# mapleCUx_med_022.net
KiCad netlist of a schematic drawn in EAGLE
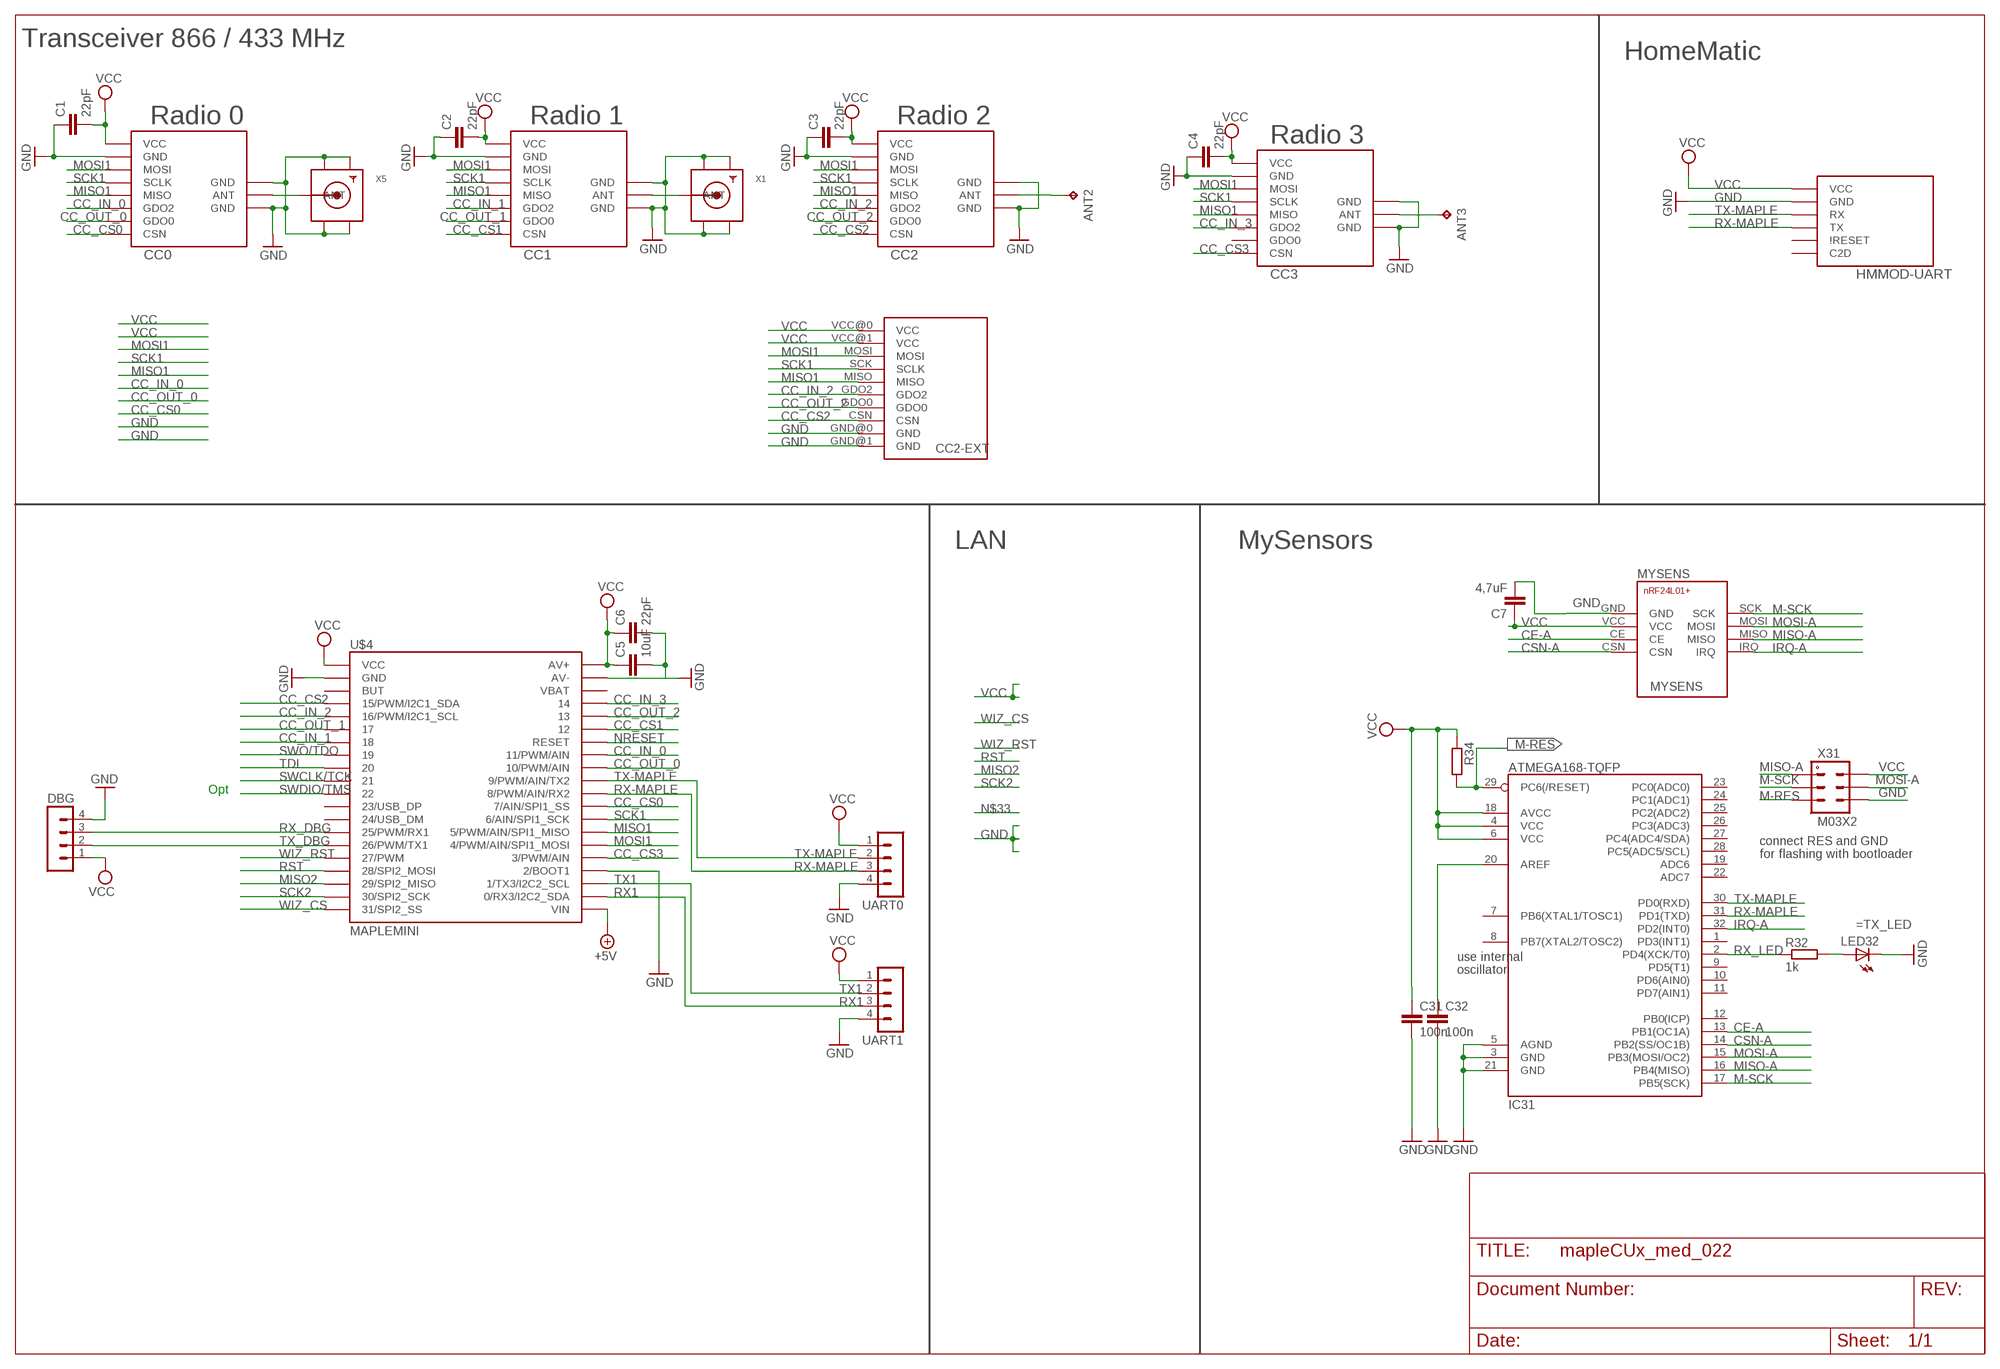
[diagram p0: schematic, sheet 1]

(export (version "E")
  (design (tool "Eeschema 10.0.6"))
  (components
    (comp (ref "ANT2")
      (value "TPPAD1-13")
      (footprint "eagle-import:P1-13")
      (libsource (lib "eagle-import") (part "TPPAD1-13"))
    )
    (comp (ref "ANT3")
      (value "TPPAD1-13")
      (footprint "eagle-import:P1-13")
      (libsource (lib "eagle-import") (part "TPPAD1-13"))
    )
    (comp (ref "C1")
      (value "22pF")
      (footprint "eagle-import:C0805")
      (libsource (lib "eagle-import") (part "C-EUC0805"))
    )
    (comp (ref "C2")
      (value "22pF")
      (footprint "eagle-import:C0805")
      (libsource (lib "eagle-import") (part "C-EUC0805"))
    )
    (comp (ref "C3")
      (value "22pF")
      (footprint "eagle-import:C0805")
      (libsource (lib "eagle-import") (part "C-EUC0805"))
    )
    (comp (ref "C4")
      (value "22pF")
      (footprint "eagle-import:C0805")
      (libsource (lib "eagle-import") (part "C-EUC0805"))
    )
    (comp (ref "C5")
      (value "10uF")
      (footprint "eagle-import:C1210")
      (libsource (lib "eagle-import") (part "C-EUC1210"))
    )
    (comp (ref "C6")
      (value "22pF")
      (footprint "eagle-import:C0805")
      (libsource (lib "eagle-import") (part "C-EUC0805"))
    )
    (comp (ref "C7")
      (value "4,7uF")
      (footprint "eagle-import:C1210")
      (libsource (lib "eagle-import") (part "C-EUC1210"))
    )
    (comp (ref "C31")
      (value "100n")
      (footprint "eagle-import:C0805")
      (libsource (lib "eagle-import") (part "C-EUC0805"))
    )
    (comp (ref "C32")
      (value "100n")
      (footprint "eagle-import:C0805")
      (libsource (lib "eagle-import") (part "C-EUC0805"))
    )
    (comp (ref "CC0")
      (value "CC1101")
      (footprint "eagle-import:CC1101_MODULE1_SMD")
      (libsource (lib "eagle-import") (part "CC1101_MODULE1SMD"))
    )
    (comp (ref "CC1")
      (value "CC1101_MODULE1SMD")
      (footprint "eagle-import:CC1101_MODULE1_SMD")
      (libsource (lib "eagle-import") (part "CC1101_MODULE1SMD"))
    )
    (comp (ref "CC2")
      (value "CC1101_MODULE1SMD")
      (footprint "eagle-import:CC1101_MODULE1_SMD")
      (libsource (lib "eagle-import") (part "CC1101_MODULE1SMD"))
    )
    (comp (ref "CC2-EXT")
      (value "CC1101_MODULE3_DIL")
      (footprint "eagle-import:CC1101_MODULE3_DIL")
      (libsource (lib "eagle-import") (part "CC1101_MODULE3_DIL"))
    )
    (comp (ref "CC3")
      (value "CC1101_MODULE1SMD")
      (footprint "eagle-import:CC1101_MODULE1_SMD")
      (libsource (lib "eagle-import") (part "CC1101_MODULE1SMD"))
    )
    (comp (ref "DBG")
      (value "MA04-1")
      (footprint "eagle-import:MA04-1")
      (libsource (lib "eagle-import") (part "MA04-1"))
    )
    (comp (ref "HMMOD-UART")
      (value "HM-MOD-UARTDIL")
      (footprint "eagle-import:HM-MOD-UART-DIL")
      (libsource (lib "eagle-import") (part "HM-MOD-UARTDIL"))
    )
    (comp (ref "IC31")
      (value "ATMEGA168-TQFP")
      (footprint "eagle-import:TQFP32-08")
      (libsource (lib "eagle-import") (part "ATMEGA168-TQFP"))
    )
    (comp (ref "LED32")
      (value "LEDCHIPLED_0805")
      (footprint "eagle-import:CHIPLED_0805")
      (libsource (lib "eagle-import") (part "LEDCHIPLED_0805"))
    )
    (comp (ref "MYSENS")
      (value "NRF24L01+SMD")
      (footprint "eagle-import:NRF24L01+SMD")
      (libsource (lib "eagle-import") (part "NRF24L01+SMD"))
    )
    (comp (ref "R32")
      (value "1k")
      (footprint "eagle-import:R0805")
      (libsource (lib "eagle-import") (part "R-EU_R0805"))
    )
    (comp (ref "R34")
      (value "R-EU_R0805")
      (footprint "eagle-import:R0805")
      (libsource (lib "eagle-import") (part "R-EU_R0805"))
    )
    (comp (ref "U$4")
      (value "MAPLEMINI")
      (footprint "eagle-import:20-DIP")
      (libsource (lib "eagle-import") (part "MAPLEMINI"))
    )
    (comp (ref "UART0")
      (value "MA04-1")
      (footprint "eagle-import:MA04-1")
      (libsource (lib "eagle-import") (part "MA04-1"))
    )
    (comp (ref "UART1")
      (value "MA04-1")
      (footprint "eagle-import:MA04-1")
      (libsource (lib "eagle-import") (part "MA04-1"))
    )
    (comp (ref "X1")
      (value "SMACONNECTOR_EDGE_UFL")
      (footprint "eagle-import:SMA_EDGELAUNCH_UFL")
      (libsource (lib "eagle-import") (part "SMACONNECTOR_EDGE_UFL"))
    )
    (comp (ref "X5")
      (value "SMACONNECTOR_EDGE_UFL")
      (footprint "eagle-import:SMA_EDGELAUNCH_UFL")
      (libsource (lib "eagle-import") (part "SMACONNECTOR_EDGE_UFL"))
    )
    (comp (ref "X31")
      (value "M03X2")
      (footprint "eagle-import:2X03-1.27MM_SMD")
      (libsource (lib "eagle-import") (part "M03X2"))
    )
  )
  (nets
    (net (code "1") (name "+5V") (class "Default")
      (node (ref "U$4") (pin "21") (pinfunction "VIN_21") (pintype "bidirectional"))
    )
    (net (code "2") (name "/CC_CS0") (class "Default")
      (node (ref "CC0") (pin "CSN") (pinfunction "CSN_CSN") (pintype "bidirectional"))
      (node (ref "U$4") (pin "29") (pinfunction "7/AIN/SPI1_SS_29") (pintype "bidirectional"))
    )
    (net (code "3") (name "/CC_CS1") (class "Default")
      (node (ref "CC1") (pin "CSN") (pinfunction "CSN_CSN") (pintype "bidirectional"))
      (node (ref "U$4") (pin "35") (pinfunction "12_35") (pintype "bidirectional"))
    )
    (net (code "4") (name "/CC_CS2") (class "Default")
      (node (ref "CC2") (pin "CSN") (pinfunction "CSN_CSN") (pintype "bidirectional"))
      (node (ref "CC2-EXT") (pin "CSN") (pinfunction "CSN_CSN") (pintype "bidirectional"))
      (node (ref "U$4") (pin "4") (pinfunction "15/PWM/I2C1_SDA_4") (pintype "bidirectional"))
    )
    (net (code "5") (name "/CC_CS3") (class "Default")
      (node (ref "CC3") (pin "CSN") (pinfunction "CSN_CSN") (pintype "bidirectional"))
      (node (ref "U$4") (pin "25") (pinfunction "3/PWM/AIN_25") (pintype "bidirectional"))
    )
    (net (code "6") (name "/CC_IN_0") (class "Default")
      (node (ref "CC0") (pin "GDO2") (pinfunction "GDO2_GDO2") (pintype "bidirectional"))
      (node (ref "U$4") (pin "33") (pinfunction "11/PWM/AIN_33") (pintype "bidirectional"))
    )
    (net (code "7") (name "/CC_IN_1") (class "Default")
      (node (ref "CC1") (pin "GDO2") (pinfunction "GDO2_GDO2") (pintype "bidirectional"))
      (node (ref "U$4") (pin "7") (pinfunction "18_7") (pintype "bidirectional"))
    )
    (net (code "8") (name "/CC_IN_2") (class "Default")
      (node (ref "CC2") (pin "GDO2") (pinfunction "GDO2_GDO2") (pintype "bidirectional"))
      (node (ref "CC2-EXT") (pin "GDO2") (pinfunction "GDO2_GDO2") (pintype "bidirectional"))
      (node (ref "U$4") (pin "5") (pinfunction "16/PWM/I2C1_SCL_5") (pintype "bidirectional"))
    )
    (net (code "9") (name "/CC_IN_3") (class "Default")
      (node (ref "CC3") (pin "GDO2") (pinfunction "GDO2_GDO2") (pintype "bidirectional"))
      (node (ref "U$4") (pin "37") (pinfunction "14_37") (pintype "bidirectional"))
    )
    (net (code "10") (name "/CC_OUT_0") (class "Default")
      (node (ref "CC0") (pin "GDO0") (pinfunction "GDO0_GDO0") (pintype "bidirectional"))
      (node (ref "U$4") (pin "32") (pinfunction "10/PWM/AIN_32") (pintype "bidirectional"))
    )
    (net (code "11") (name "/CC_OUT_1") (class "Default")
      (node (ref "CC1") (pin "GDO0") (pinfunction "GDO0_GDO0") (pintype "bidirectional"))
      (node (ref "U$4") (pin "6") (pinfunction "17_6") (pintype "bidirectional"))
    )
    (net (code "12") (name "/CC_OUT_2") (class "Default")
      (node (ref "CC2") (pin "GDO0") (pinfunction "GDO0_GDO0") (pintype "bidirectional"))
      (node (ref "CC2-EXT") (pin "GDO0") (pinfunction "GDO0_GDO0") (pintype "bidirectional"))
      (node (ref "U$4") (pin "36") (pinfunction "13_36") (pintype "bidirectional"))
    )
    (net (code "13") (name "/CE-A") (class "Default")
      (node (ref "IC31") (pin "13") (pinfunction "PB1(OC1A)_13") (pintype "bidirectional"))
      (node (ref "MYSENS") (pin "CE") (pinfunction "CE_CE") (pintype "bidirectional"))
    )
    (net (code "14") (name "/CSN-A") (class "Default")
      (node (ref "IC31") (pin "14") (pinfunction "PB2(SS/OC1B)_14") (pintype "bidirectional"))
      (node (ref "MYSENS") (pin "CSN") (pinfunction "CSN_CSN") (pintype "bidirectional"))
    )
    (net (code "15") (name "/IRQ-A") (class "Default")
      (node (ref "IC31") (pin "32") (pinfunction "PD2(INT0)_32") (pintype "bidirectional"))
      (node (ref "MYSENS") (pin "IRQ") (pinfunction "IRQ_IRQ") (pintype "bidirectional"))
    )
    (net (code "16") (name "/M-RES") (class "Default")
      (node (ref "IC31") (pin "29") (pinfunction "PC6(/RESET)_29") (pintype "bidirectional"))
      (node (ref "R34") (pin "2") (pinfunction "2_2") (pintype "passive"))
      (node (ref "X31") (pin "P$5") (pinfunction "5_P$5") (pintype "passive"))
    )
    (net (code "17") (name "/M-SCK") (class "Default")
      (node (ref "IC31") (pin "17") (pinfunction "PB5(SCK)_17") (pintype "bidirectional"))
      (node (ref "MYSENS") (pin "SCK") (pinfunction "SCK_SCK") (pintype "bidirectional"))
      (node (ref "X31") (pin "P$3") (pinfunction "3_P$3") (pintype "passive"))
    )
    (net (code "18") (name "/MISO-A") (class "Default")
      (node (ref "IC31") (pin "16") (pinfunction "PB4(MISO)_16") (pintype "bidirectional"))
      (node (ref "MYSENS") (pin "MISO") (pinfunction "MISO_MISO") (pintype "bidirectional"))
      (node (ref "X31") (pin "P$1") (pinfunction "1_P$1") (pintype "passive"))
    )
    (net (code "19") (name "/MISO1") (class "Default")
      (node (ref "CC0") (pin "MISO") (pinfunction "MISO_MISO") (pintype "bidirectional"))
      (node (ref "CC1") (pin "MISO") (pinfunction "MISO_MISO") (pintype "bidirectional"))
      (node (ref "CC2") (pin "MISO") (pinfunction "MISO_MISO") (pintype "bidirectional"))
      (node (ref "CC2-EXT") (pin "MISO") (pinfunction "MISO_MISO") (pintype "bidirectional"))
      (node (ref "CC3") (pin "MISO") (pinfunction "MISO_MISO") (pintype "bidirectional"))
      (node (ref "U$4") (pin "27") (pinfunction "5/PWM/AIN/SPI1_MISO_27") (pintype "bidirectional"))
    )
    (net (code "20") (name "/MISO2") (class "Default")
      (node (ref "U$4") (pin "18") (pinfunction "29/SPI2_MISO_18") (pintype "bidirectional"))
    )
    (net (code "21") (name "/MOSI-A") (class "Default")
      (node (ref "IC31") (pin "15") (pinfunction "PB3(MOSI/OC2)_15") (pintype "bidirectional"))
      (node (ref "MYSENS") (pin "MOSI") (pinfunction "MOSI_MOSI") (pintype "bidirectional"))
      (node (ref "X31") (pin "P$4") (pinfunction "4_P$4") (pintype "passive"))
    )
    (net (code "22") (name "/MOSI1") (class "Default")
      (node (ref "CC0") (pin "MOSI") (pinfunction "MOSI_MOSI") (pintype "bidirectional"))
      (node (ref "CC1") (pin "MOSI") (pinfunction "MOSI_MOSI") (pintype "bidirectional"))
      (node (ref "CC2") (pin "MOSI") (pinfunction "MOSI_MOSI") (pintype "bidirectional"))
      (node (ref "CC2-EXT") (pin "MOSI") (pinfunction "MOSI_MOSI") (pintype "bidirectional"))
      (node (ref "CC3") (pin "MOSI") (pinfunction "MOSI_MOSI") (pintype "bidirectional"))
      (node (ref "U$4") (pin "26") (pinfunction "4/PWM/AIN/SPI1_MOSI_26") (pintype "bidirectional"))
    )
    (net (code "24") (name "/NRESET") (class "Default")
      (node (ref "U$4") (pin "34") (pinfunction "RESET_34") (pintype "bidirectional"))
    )
    (net (code "25") (name "/RST") (class "Default")
      (node (ref "U$4") (pin "17") (pinfunction "28/SPI2_MOSI_17") (pintype "bidirectional"))
    )
    (net (code "26") (name "/RX-MAPLE") (class "Default")
      (node (ref "HMMOD-UART") (pin "5") (pinfunction "TX_5") (pintype "bidirectional"))
      (node (ref "IC31") (pin "31") (pinfunction "PD1(TXD)_31") (pintype "bidirectional"))
      (node (ref "U$4") (pin "30") (pinfunction "8/PWM/AIN/RX2_30") (pintype "bidirectional"))
      (node (ref "UART0") (pin "3") (pinfunction "3_3") (pintype "passive"))
    )
    (net (code "27") (name "/RX1") (class "Default")
      (node (ref "U$4") (pin "22") (pinfunction "0/RX3/I2C2_SDA_22") (pintype "bidirectional"))
      (node (ref "UART1") (pin "3") (pinfunction "3_3") (pintype "passive"))
    )
    (net (code "28") (name "/RX_DBG") (class "Default")
      (node (ref "DBG") (pin "3") (pinfunction "3_3") (pintype "passive"))
      (node (ref "U$4") (pin "14") (pinfunction "25/PWM/RX1_14") (pintype "bidirectional"))
    )
    (net (code "29") (name "/RX_LED") (class "Default")
      (node (ref "IC31") (pin "2") (pinfunction "PD4(XCK/T0)_2") (pintype "bidirectional"))
      (node (ref "R32") (pin "1") (pinfunction "1_1") (pintype "passive"))
    )
    (net (code "30") (name "/SCK1") (class "Default")
      (node (ref "CC0") (pin "SCLK") (pinfunction "SCLK_SCLK") (pintype "bidirectional"))
      (node (ref "CC1") (pin "SCLK") (pinfunction "SCLK_SCLK") (pintype "bidirectional"))
      (node (ref "CC2") (pin "SCLK") (pinfunction "SCLK_SCLK") (pintype "bidirectional"))
      (node (ref "CC2-EXT") (pin "SCK") (pinfunction "SCLK_SCK") (pintype "bidirectional"))
      (node (ref "CC3") (pin "SCLK") (pinfunction "SCLK_SCLK") (pintype "bidirectional"))
      (node (ref "U$4") (pin "28") (pinfunction "6/AIN/SPI1_SCK_28") (pintype "bidirectional"))
    )
    (net (code "31") (name "/SCK2") (class "Default")
      (node (ref "U$4") (pin "19") (pinfunction "30/SPI2_SCK_19") (pintype "bidirectional"))
    )
    (net (code "32") (name "/SWCLK{slash}TCK") (class "Default")
      (node (ref "U$4") (pin "10") (pinfunction "21_10") (pintype "bidirectional"))
    )
    (net (code "33") (name "/SWDIO{slash}TMS") (class "Default")
      (node (ref "U$4") (pin "11") (pinfunction "22_11") (pintype "bidirectional"))
    )
    (net (code "34") (name "/SWO{slash}TDO") (class "Default")
      (node (ref "U$4") (pin "8") (pinfunction "19_8") (pintype "bidirectional"))
    )
    (net (code "35") (name "/TDI") (class "Default")
      (node (ref "U$4") (pin "9") (pinfunction "20_9") (pintype "bidirectional"))
    )
    (net (code "36") (name "/TX-MAPLE") (class "Default")
      (node (ref "HMMOD-UART") (pin "6") (pinfunction "RX_6") (pintype "bidirectional"))
      (node (ref "IC31") (pin "30") (pinfunction "PD0(RXD)_30") (pintype "bidirectional"))
      (node (ref "U$4") (pin "31") (pinfunction "9/PWM/AIN/TX2_31") (pintype "bidirectional"))
      (node (ref "UART0") (pin "2") (pinfunction "2_2") (pintype "passive"))
    )
    (net (code "37") (name "/TX1") (class "Default")
      (node (ref "U$4") (pin "23") (pinfunction "1/TX3/I2C2_SCL_23") (pintype "bidirectional"))
      (node (ref "UART1") (pin "2") (pinfunction "2_2") (pintype "passive"))
    )
    (net (code "38") (name "/TX_DBG") (class "Default")
      (node (ref "DBG") (pin "2") (pinfunction "2_2") (pintype "passive"))
      (node (ref "U$4") (pin "15") (pinfunction "26/PWM/TX1_15") (pintype "bidirectional"))
    )
    (net (code "39") (name "/WIZ_CS") (class "Default")
      (node (ref "U$4") (pin "20") (pinfunction "31/SPI2_SS_20") (pintype "bidirectional"))
    )
    (net (code "40") (name "/WIZ_RST") (class "Default")
      (node (ref "U$4") (pin "16") (pinfunction "27/PWM_16") (pintype "bidirectional"))
    )
    (net (code "41") (name "GND") (class "Default")
      (node (ref "C1") (pin "1") (pinfunction "1_1") (pintype "passive"))
      (node (ref "C2") (pin "1") (pinfunction "1_1") (pintype "passive"))
      (node (ref "C3") (pin "1") (pinfunction "1_1") (pintype "passive"))
      (node (ref "C31") (pin "2") (pinfunction "2_2") (pintype "passive"))
      (node (ref "C32") (pin "2") (pinfunction "2_2") (pintype "passive"))
      (node (ref "C4") (pin "1") (pinfunction "1_1") (pintype "passive"))
      (node (ref "C5") (pin "2") (pinfunction "2_2") (pintype "passive"))
      (node (ref "C6") (pin "2") (pinfunction "2_2") (pintype "passive"))
      (node (ref "C7") (pin "2") (pinfunction "2_2") (pintype "passive"))
      (node (ref "CC0") (pin "GND@0") (pinfunction "GND_GND@0") (pintype "power_in"))
      (node (ref "CC0") (pin "GND@1") (pinfunction "GND_GND@1") (pintype "power_in"))
      (node (ref "CC0") (pin "GND@2") (pinfunction "GND_GND@2") (pintype "power_in"))
      (node (ref "CC1") (pin "GND@0") (pinfunction "GND_GND@0") (pintype "power_in"))
      (node (ref "CC1") (pin "GND@1") (pinfunction "GND_GND@1") (pintype "power_in"))
      (node (ref "CC1") (pin "GND@2") (pinfunction "GND_GND@2") (pintype "power_in"))
      (node (ref "CC2") (pin "GND@0") (pinfunction "GND_GND@0") (pintype "power_in"))
      (node (ref "CC2") (pin "GND@1") (pinfunction "GND_GND@1") (pintype "power_in"))
      (node (ref "CC2") (pin "GND@2") (pinfunction "GND_GND@2") (pintype "power_in"))
      (node (ref "CC2-EXT") (pin "GND@0") (pinfunction "GND_GND@0") (pintype "power_in"))
      (node (ref "CC2-EXT") (pin "GND@1") (pinfunction "GND_GND@1") (pintype "power_in"))
      (node (ref "CC3") (pin "GND@0") (pinfunction "GND_GND@0") (pintype "power_in"))
      (node (ref "CC3") (pin "GND@1") (pinfunction "GND_GND@1") (pintype "power_in"))
      (node (ref "CC3") (pin "GND@2") (pinfunction "GND_GND@2") (pintype "power_in"))
      (node (ref "DBG") (pin "4") (pinfunction "4_4") (pintype "passive"))
      (node (ref "HMMOD-UART") (pin "2") (pinfunction "GND_2") (pintype "power_in"))
      (node (ref "IC31") (pin "21") (pinfunction "GND_21") (pintype "bidirectional"))
      (node (ref "IC31") (pin "3") (pinfunction "GND_3") (pintype "bidirectional"))
      (node (ref "IC31") (pin "5") (pinfunction "AGND_5") (pintype "bidirectional"))
      (node (ref "LED32") (pin "C") (pinfunction "C_C") (pintype "passive"))
      (node (ref "MYSENS") (pin "GND") (pinfunction "GND_GND") (pintype "power_in"))
      (node (ref "U$4") (pin "2") (pinfunction "GND_2") (pintype "bidirectional"))
      (node (ref "U$4") (pin "24") (pinfunction "2/BOOT1_24") (pintype "bidirectional"))
      (node (ref "U$4") (pin "39") (pinfunction "AV-_39") (pintype "bidirectional"))
      (node (ref "UART0") (pin "4") (pinfunction "4_4") (pintype "passive"))
      (node (ref "UART1") (pin "4") (pinfunction "4_4") (pintype "passive"))
      (node (ref "X1") (pin "GND@1") (pinfunction "GND1_GND@1") (pintype "power_in"))
      (node (ref "X1") (pin "GND@2") (pinfunction "GND2_GND@2") (pintype "power_in"))
      (node (ref "X1") (pin "GND@3") (pinfunction "GND3_GND@3") (pintype "power_in"))
      (node (ref "X1") (pin "GND@4") (pinfunction "GND4_GND@4") (pintype "power_in"))
      (node (ref "X31") (pin "P$6") (pinfunction "6_P$6") (pintype "passive"))
      (node (ref "X5") (pin "GND@1") (pinfunction "GND1_GND@1") (pintype "power_in"))
      (node (ref "X5") (pin "GND@2") (pinfunction "GND2_GND@2") (pintype "power_in"))
      (node (ref "X5") (pin "GND@3") (pinfunction "GND3_GND@3") (pintype "power_in"))
      (node (ref "X5") (pin "GND@4") (pinfunction "GND4_GND@4") (pintype "power_in"))
    )
    (net (code "42") (name "Net-(ANT2-PadTP)") (class "Default")
      (node (ref "ANT2") (pin "TP") (pinfunction "TP_TP") (pintype "input"))
      (node (ref "CC2") (pin "ANT") (pinfunction "ANT_ANT") (pintype "output"))
    )
    (net (code "43") (name "Net-(ANT3-PadTP)") (class "Default")
      (node (ref "ANT3") (pin "TP") (pinfunction "TP_TP") (pintype "input"))
      (node (ref "CC3") (pin "ANT") (pinfunction "ANT_ANT") (pintype "output"))
    )
    (net (code "44") (name "Net-(IC31-AREF)") (class "Default")
      (node (ref "C32") (pin "1") (pinfunction "1_1") (pintype "passive"))
      (node (ref "IC31") (pin "20") (pinfunction "AREF_20") (pintype "bidirectional"))
    )
    (net (code "45") (name "Net-(LED32-PadA)") (class "Default")
      (node (ref "LED32") (pin "A") (pinfunction "A_A") (pintype "passive"))
      (node (ref "R32") (pin "2") (pinfunction "2_2") (pintype "passive"))
    )
    (net (code "46") (name "Net-(X1-ANT)") (class "Default")
      (node (ref "CC1") (pin "ANT") (pinfunction "ANT_ANT") (pintype "output"))
      (node (ref "X1") (pin "P") (pinfunction "ANT_P") (pintype "bidirectional"))
    )
    (net (code "47") (name "Net-(X5-ANT)") (class "Default")
      (node (ref "CC0") (pin "ANT") (pinfunction "ANT_ANT") (pintype "output"))
      (node (ref "X5") (pin "P") (pinfunction "ANT_P") (pintype "bidirectional"))
    )
    (net (code "48") (name "VCC") (class "Default")
      (node (ref "C1") (pin "2") (pinfunction "2_2") (pintype "passive"))
      (node (ref "C2") (pin "2") (pinfunction "2_2") (pintype "passive"))
      (node (ref "C3") (pin "2") (pinfunction "2_2") (pintype "passive"))
      (node (ref "C31") (pin "1") (pinfunction "1_1") (pintype "passive"))
      (node (ref "C4") (pin "2") (pinfunction "2_2") (pintype "passive"))
      (node (ref "C5") (pin "1") (pinfunction "1_1") (pintype "passive"))
      (node (ref "C6") (pin "1") (pinfunction "1_1") (pintype "passive"))
      (node (ref "C7") (pin "1") (pinfunction "1_1") (pintype "passive"))
      (node (ref "CC0") (pin "VCC") (pinfunction "VCC_VCC") (pintype "power_in"))
      (node (ref "CC1") (pin "VCC") (pinfunction "VCC_VCC") (pintype "power_in"))
      (node (ref "CC2") (pin "VCC") (pinfunction "VCC_VCC") (pintype "power_in"))
      (node (ref "CC2-EXT") (pin "VCC@0") (pinfunction "VCC_VCC@0") (pintype "power_in"))
      (node (ref "CC2-EXT") (pin "VCC@1") (pinfunction "VCC_VCC@1") (pintype "power_in"))
      (node (ref "CC3") (pin "VCC") (pinfunction "VCC_VCC") (pintype "power_in"))
      (node (ref "DBG") (pin "1") (pinfunction "1_1") (pintype "passive"))
      (node (ref "HMMOD-UART") (pin "1") (pinfunction "VCC_1") (pintype "power_in"))
      (node (ref "IC31") (pin "18") (pinfunction "AVCC_18") (pintype "bidirectional"))
      (node (ref "IC31") (pin "4") (pinfunction "VCC_4") (pintype "bidirectional"))
      (node (ref "IC31") (pin "6") (pinfunction "VCC_6") (pintype "bidirectional"))
      (node (ref "MYSENS") (pin "VCC") (pinfunction "VCC_VCC") (pintype "power_in"))
      (node (ref "R34") (pin "1") (pinfunction "1_1") (pintype "passive"))
      (node (ref "U$4") (pin "1") (pinfunction "VCC_1") (pintype "bidirectional"))
      (node (ref "U$4") (pin "40") (pinfunction "AV+_40") (pintype "bidirectional"))
      (node (ref "UART0") (pin "1") (pinfunction "1_1") (pintype "passive"))
      (node (ref "UART1") (pin "1") (pinfunction "1_1") (pintype "passive"))
      (node (ref "X31") (pin "P$2") (pinfunction "2_P$2") (pintype "passive"))
    )
    (net (code "49") (name "unconnected-(CC3-PadGDO0)") (class "Default")
      (node (ref "CC3") (pin "GDO0") (pinfunction "GDO0_GDO0") (pintype "bidirectional"))
    )
    (net (code "50") (name "unconnected-(HMMOD-UART-C2D-Pad3)") (class "Default")
      (node (ref "HMMOD-UART") (pin "3") (pinfunction "C2D_3") (pintype "bidirectional"))
    )
    (net (code "51") (name "unconnected-(HMMOD-UART-\\~{RESET}-Pad4)") (class "Default")
      (node (ref "HMMOD-UART") (pin "4") (pinfunction "\\~{RESET}_4") (pintype "bidirectional"))
    )
    (net (code "52") (name "unconnected-(IC31-ADC6-Pad19)") (class "Default")
      (node (ref "IC31") (pin "19") (pinfunction "ADC6_19") (pintype "bidirectional"))
    )
    (net (code "53") (name "unconnected-(IC31-ADC7-Pad22)") (class "Default")
      (node (ref "IC31") (pin "22") (pinfunction "ADC7_22") (pintype "bidirectional"))
    )
    (net (code "54") (name "unconnected-(IC31-PB0(ICP)-Pad12)") (class "Default")
      (node (ref "IC31") (pin "12") (pinfunction "PB0(ICP)_12") (pintype "bidirectional"))
    )
    (net (code "55") (name "unconnected-(IC31-PB6(XTAL1{slash}TOSC1)-Pad7)") (class "Default")
      (node (ref "IC31") (pin "7") (pinfunction "PB6(XTAL1/TOSC1)_7") (pintype "bidirectional"))
    )
    (net (code "56") (name "unconnected-(IC31-PB7(XTAL2{slash}TOSC2)-Pad8)") (class "Default")
      (node (ref "IC31") (pin "8") (pinfunction "PB7(XTAL2/TOSC2)_8") (pintype "bidirectional"))
    )
    (net (code "57") (name "unconnected-(IC31-PC0(ADC0)-Pad23)") (class "Default")
      (node (ref "IC31") (pin "23") (pinfunction "PC0(ADC0)_23") (pintype "bidirectional"))
    )
    (net (code "58") (name "unconnected-(IC31-PC1(ADC1)-Pad24)") (class "Default")
      (node (ref "IC31") (pin "24") (pinfunction "PC1(ADC1)_24") (pintype "bidirectional"))
    )
    (net (code "59") (name "unconnected-(IC31-PC2(ADC2)-Pad25)") (class "Default")
      (node (ref "IC31") (pin "25") (pinfunction "PC2(ADC2)_25") (pintype "bidirectional"))
    )
    (net (code "60") (name "unconnected-(IC31-PC3(ADC3)-Pad26)") (class "Default")
      (node (ref "IC31") (pin "26") (pinfunction "PC3(ADC3)_26") (pintype "bidirectional"))
    )
    (net (code "61") (name "unconnected-(IC31-PC4(ADC4{slash}SDA)-Pad27)") (class "Default")
      (node (ref "IC31") (pin "27") (pinfunction "PC4(ADC4/SDA)_27") (pintype "bidirectional"))
    )
    (net (code "62") (name "unconnected-(IC31-PC5(ADC5{slash}SCL)-Pad28)") (class "Default")
      (node (ref "IC31") (pin "28") (pinfunction "PC5(ADC5/SCL)_28") (pintype "bidirectional"))
    )
    (net (code "63") (name "unconnected-(IC31-PD3(INT1)-Pad1)") (class "Default")
      (node (ref "IC31") (pin "1") (pinfunction "PD3(INT1)_1") (pintype "bidirectional"))
    )
    (net (code "64") (name "unconnected-(IC31-PD5(T1)-Pad9)") (class "Default")
      (node (ref "IC31") (pin "9") (pinfunction "PD5(T1)_9") (pintype "bidirectional"))
    )
    (net (code "65") (name "unconnected-(IC31-PD6(AIN0)-Pad10)") (class "Default")
      (node (ref "IC31") (pin "10") (pinfunction "PD6(AIN0)_10") (pintype "bidirectional"))
    )
    (net (code "66") (name "unconnected-(IC31-PD7(AIN1)-Pad11)") (class "Default")
      (node (ref "IC31") (pin "11") (pinfunction "PD7(AIN1)_11") (pintype "bidirectional"))
    )
    (net (code "67") (name "unconnected-(U$4-23{slash}USB_DP-Pad12)") (class "Default")
      (node (ref "U$4") (pin "12") (pinfunction "23/USB_DP_12") (pintype "bidirectional"))
    )
    (net (code "68") (name "unconnected-(U$4-24{slash}USB_DM-Pad13)") (class "Default")
      (node (ref "U$4") (pin "13") (pinfunction "24/USB_DM_13") (pintype "bidirectional"))
    )
    (net (code "69") (name "unconnected-(U$4-BUT-Pad3)") (class "Default")
      (node (ref "U$4") (pin "3") (pinfunction "BUT_3") (pintype "bidirectional"))
    )
    (net (code "70") (name "unconnected-(U$4-VBAT-Pad38)") (class "Default")
      (node (ref "U$4") (pin "38") (pinfunction "VBAT_38") (pintype "bidirectional"))
    )
  )
)
